# Sheet2.net
KiCad netlist of a schematic drawn in Altium Designer
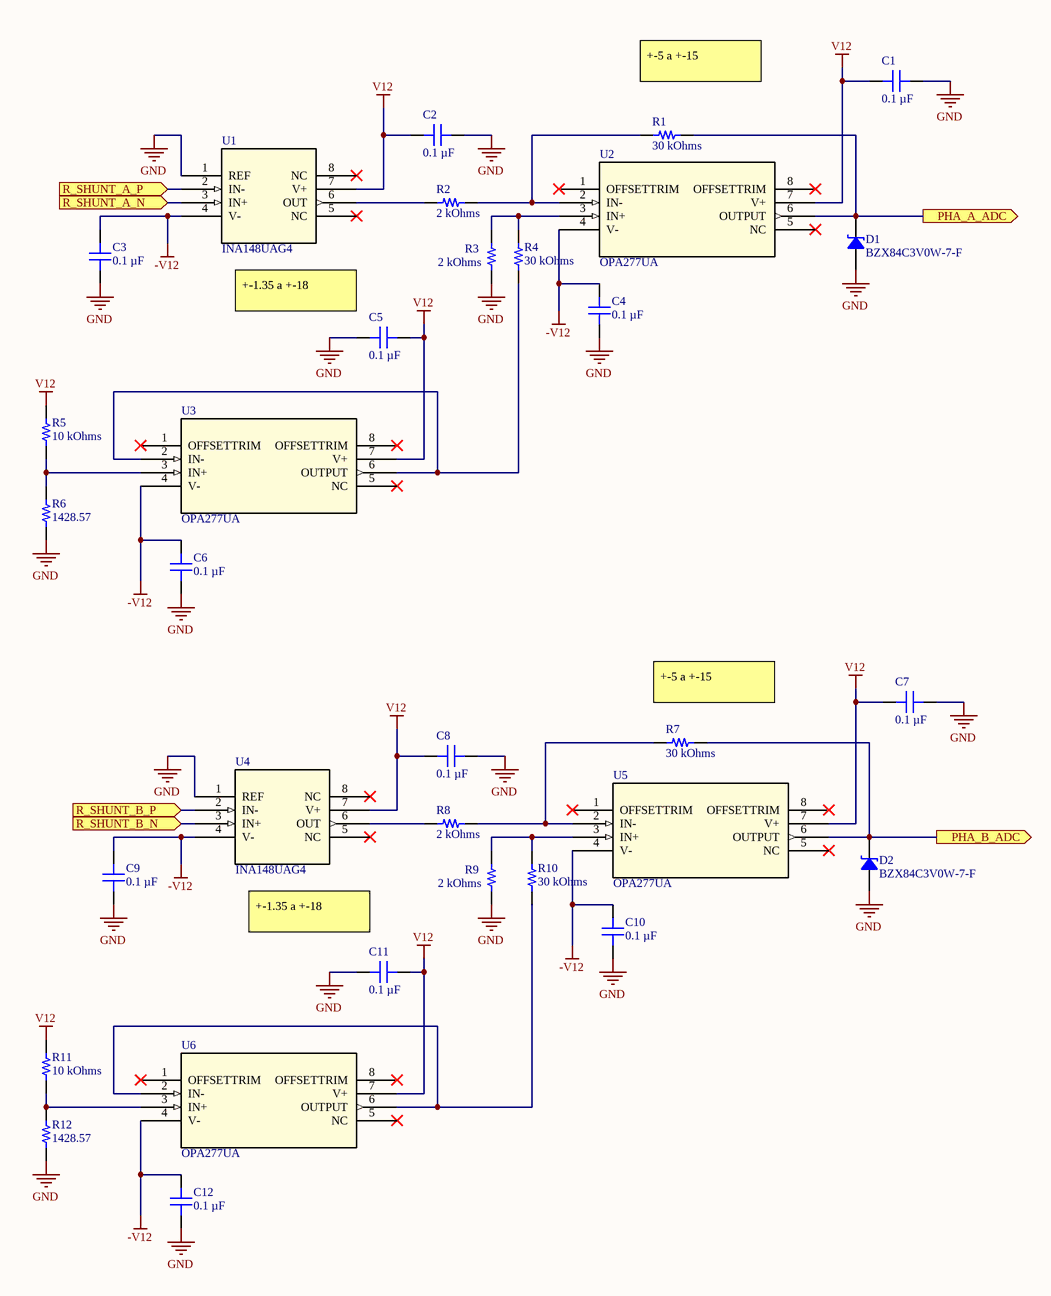
[diagram p0: Sheet2.SchDoc]

(export (version "E")
  (design (tool "Eeschema 10.0.6"))
  (components
    (comp (ref "C1")
      (value "0.1 µF")
      (footprint "CAP 0805_2012")
      (description "CAP CER 0.1UF 50V X7R 0805")
      (fields (field (name "PART NUMBER") "CC0805MRX7R9BB104") (field (name "MANUFACTURER") "Yageo"))
      (libsource (lib "Celestial Altium Library - altium_library") (part "Capacitor"))
    )
    (comp (ref "C2")
      (value "0.1 µF")
      (footprint "CAP 0805_2012")
      (description "CAP CER 0.1UF 50V X7R 0805")
      (fields (field (name "PART NUMBER") "CC0805MRX7R9BB104") (field (name "MANUFACTURER") "Yageo"))
      (libsource (lib "Celestial Altium Library - altium_library") (part "Capacitor"))
    )
    (comp (ref "C3")
      (value "0.1 µF")
      (footprint "CAP 0805_2012")
      (description "CAP CER 0.1UF 50V X7R 0805")
      (fields (field (name "PART NUMBER") "CC0805MRX7R9BB104") (field (name "MANUFACTURER") "Yageo"))
      (libsource (lib "Celestial Altium Library - altium_library") (part "Capacitor"))
    )
    (comp (ref "C4")
      (value "0.1 µF")
      (footprint "CAP 0805_2012")
      (description "CAP CER 0.1UF 50V X7R 0805")
      (fields (field (name "PART NUMBER") "CC0805MRX7R9BB104") (field (name "MANUFACTURER") "Yageo"))
      (libsource (lib "Celestial Altium Library - altium_library") (part "Capacitor"))
    )
    (comp (ref "C5")
      (value "0.1 µF")
      (footprint "CAP 0805_2012")
      (description "CAP CER 0.1UF 50V X7R 0805")
      (fields (field (name "PART NUMBER") "CC0805MRX7R9BB104") (field (name "MANUFACTURER") "Yageo"))
      (libsource (lib "Celestial Altium Library - altium_library") (part "Capacitor"))
    )
    (comp (ref "C6")
      (value "0.1 µF")
      (footprint "CAP 0805_2012")
      (description "CAP CER 0.1UF 50V X7R 0805")
      (fields (field (name "PART NUMBER") "CC0805MRX7R9BB104") (field (name "MANUFACTURER") "Yageo"))
      (libsource (lib "Celestial Altium Library - altium_library") (part "Capacitor"))
    )
    (comp (ref "C7")
      (value "0.1 µF")
      (footprint "CAP 0805_2012")
      (description "CAP CER 0.1UF 50V X7R 0805")
      (fields (field (name "PART NUMBER") "CC0805MRX7R9BB104") (field (name "MANUFACTURER") "Yageo"))
      (libsource (lib "Celestial Altium Library - altium_library") (part "Capacitor"))
    )
    (comp (ref "C8")
      (value "0.1 µF")
      (footprint "CAP 0805_2012")
      (description "CAP CER 0.1UF 50V X7R 0805")
      (fields (field (name "PART NUMBER") "CC0805MRX7R9BB104") (field (name "MANUFACTURER") "Yageo"))
      (libsource (lib "Celestial Altium Library - altium_library") (part "Capacitor"))
    )
    (comp (ref "C9")
      (value "0.1 µF")
      (footprint "CAP 0805_2012")
      (description "CAP CER 0.1UF 50V X7R 0805")
      (fields (field (name "PART NUMBER") "CC0805MRX7R9BB104") (field (name "MANUFACTURER") "Yageo"))
      (libsource (lib "Celestial Altium Library - altium_library") (part "Capacitor"))
    )
    (comp (ref "C10")
      (value "0.1 µF")
      (footprint "CAP 0805_2012")
      (description "CAP CER 0.1UF 50V X7R 0805")
      (fields (field (name "PART NUMBER") "CC0805MRX7R9BB104") (field (name "MANUFACTURER") "Yageo"))
      (libsource (lib "Celestial Altium Library - altium_library") (part "Capacitor"))
    )
    (comp (ref "C11")
      (value "0.1 µF")
      (footprint "CAP 0805_2012")
      (description "CAP CER 0.1UF 50V X7R 0805")
      (fields (field (name "PART NUMBER") "CC0805MRX7R9BB104") (field (name "MANUFACTURER") "Yageo"))
      (libsource (lib "Celestial Altium Library - altium_library") (part "Capacitor"))
    )
    (comp (ref "C12")
      (value "0.1 µF")
      (footprint "CAP 0805_2012")
      (description "CAP CER 0.1UF 50V X7R 0805")
      (fields (field (name "PART NUMBER") "CC0805MRX7R9BB104") (field (name "MANUFACTURER") "Yageo"))
      (libsource (lib "Celestial Altium Library - altium_library") (part "Capacitor"))
    )
    (comp (ref "D1")
      (value "BZX84C3V0W-7-F")
      (footprint "DIODES SOT-323-3")
      (description "DIODE ZENER 3V 200MW SOT323")
      (fields (field (name "MANUFACTURER") "Diodes Incorporated") (field (name "TOLERANCE") "±7%"))
      (libsource (lib "Celestial Altium Library - altium_library") (part "Diode Zener"))
    )
    (comp (ref "D2")
      (value "BZX84C3V0W-7-F")
      (footprint "DIODES SOT-323-3")
      (description "DIODE ZENER 3V 200MW SOT323")
      (fields (field (name "MANUFACTURER") "Diodes Incorporated") (field (name "TOLERANCE") "±7%"))
      (libsource (lib "Celestial Altium Library - altium_library") (part "Diode Zener"))
    )
    (comp (ref "R1")
      (value "30 kOhms")
      (footprint "RES 0805_2012")
      (description "RES SMD 200K OHM 5% 1/8W 0805")
      (fields (field (name "PART NUMBER") "CR0805-JW-204ELF") (field (name "MANUFACTURER") "Bourns Inc."))
      (libsource (lib "Celestial Altium Library - altium_library") (part "Resistor"))
    )
    (comp (ref "R2")
      (value "2 kOhms")
      (footprint "RES 0805_2012")
      (description "RES SMD 200K OHM 5% 1/8W 0805")
      (fields (field (name "PART NUMBER") "CR0805-JW-204ELF") (field (name "MANUFACTURER") "Bourns Inc."))
      (libsource (lib "Celestial Altium Library - altium_library") (part "Resistor"))
    )
    (comp (ref "R3")
      (value "2 kOhms")
      (footprint "RES 0805_2012")
      (description "RES SMD 200K OHM 5% 1/8W 0805")
      (fields (field (name "PART NUMBER") "CR0805-JW-204ELF") (field (name "MANUFACTURER") "Bourns Inc."))
      (libsource (lib "Celestial Altium Library - altium_library") (part "Resistor"))
    )
    (comp (ref "R4")
      (value "30 kOhms")
      (footprint "RES 0805_2012")
      (description "RES SMD 200K OHM 5% 1/8W 0805")
      (fields (field (name "PART NUMBER") "CR0805-JW-204ELF") (field (name "MANUFACTURER") "Bourns Inc."))
      (libsource (lib "Celestial Altium Library - altium_library") (part "Resistor"))
    )
    (comp (ref "R5")
      (value "10 kOhms")
      (footprint "RES 0805_2012")
      (description "RES SMD 200K OHM 5% 1/8W 0805")
      (fields (field (name "PART NUMBER") "CR0805-JW-204ELF") (field (name "MANUFACTURER") "Bourns Inc."))
      (libsource (lib "") (part "Resistor_1"))
    )
    (comp (ref "R6")
      (value "1428.57")
      (footprint "RES 0805_2012")
      (description "RES SMD 200K OHM 5% 1/8W 0805")
      (fields (field (name "PART NUMBER") "CR0805-JW-204ELF") (field (name "MANUFACTURER") "Bourns Inc."))
      (libsource (lib "Celestial Altium Library - altium_library") (part "Resistor"))
    )
    (comp (ref "R7")
      (value "30 kOhms")
      (footprint "RES 0805_2012")
      (description "RES SMD 200K OHM 5% 1/8W 0805")
      (fields (field (name "PART NUMBER") "CR0805-JW-204ELF") (field (name "MANUFACTURER") "Bourns Inc."))
      (libsource (lib "") (part "Resistor_1"))
    )
    (comp (ref "R8")
      (value "2 kOhms")
      (footprint "RES 0805_2012")
      (description "RES SMD 200K OHM 5% 1/8W 0805")
      (fields (field (name "PART NUMBER") "CR0805-JW-204ELF") (field (name "MANUFACTURER") "Bourns Inc."))
      (libsource (lib "Celestial Altium Library - altium_library") (part "Resistor"))
    )
    (comp (ref "R9")
      (value "2 kOhms")
      (footprint "RES 0805_2012")
      (description "RES SMD 200K OHM 5% 1/8W 0805")
      (fields (field (name "PART NUMBER") "CR0805-JW-204ELF") (field (name "MANUFACTURER") "Bourns Inc."))
      (libsource (lib "Celestial Altium Library - altium_library") (part "Resistor"))
    )
    (comp (ref "R10")
      (value "30 kOhms")
      (footprint "RES 0805_2012")
      (description "RES SMD 200K OHM 5% 1/8W 0805")
      (fields (field (name "PART NUMBER") "CR0805-JW-204ELF") (field (name "MANUFACTURER") "Bourns Inc."))
      (libsource (lib "Celestial Altium Library - altium_library") (part "Resistor"))
    )
    (comp (ref "R11")
      (value "10 kOhms")
      (footprint "RES 0805_2012")
      (description "RES SMD 200K OHM 5% 1/8W 0805")
      (fields (field (name "PART NUMBER") "CR0805-JW-204ELF") (field (name "MANUFACTURER") "Bourns Inc."))
      (libsource (lib "") (part "Resistor_1"))
    )
    (comp (ref "R12")
      (value "1428.57")
      (footprint "RES 0805_2012")
      (description "RES SMD 200K OHM 5% 1/8W 0805")
      (fields (field (name "PART NUMBER") "CR0805-JW-204ELF") (field (name "MANUFACTURER") "Bourns Inc."))
      (libsource (lib "Celestial Altium Library - altium_library") (part "Resistor"))
    )
    (comp (ref "U1")
      (value "INA148UAG4")
      (footprint "D8")
      (description "No Description Available")
      (fields (field (name "COPYRIGHT") "Copyright (C) 2023 Ultra Librarian. All rights reserved."))
      (libsource (lib "INA148UAG4") (part "INA148UAG4"))
    )
    (comp (ref "U2")
      (value "OPA277UA")
      (footprint "D8")
      (description "No Description Available")
      (fields (field (name "COPYRIGHT") "Copyright (C) 2023 Ultra Librarian. All rights reserved."))
      (libsource (lib "OPA277UA") (part "OPA277UA"))
    )
    (comp (ref "U3")
      (value "OPA277UA")
      (footprint "D8")
      (description "No Description Available")
      (fields (field (name "COPYRIGHT") "Copyright (C) 2023 Ultra Librarian. All rights reserved."))
      (libsource (lib "OPA277UA") (part "OPA277UA"))
    )
    (comp (ref "U4")
      (value "INA148UAG4")
      (footprint "D8")
      (description "No Description Available")
      (fields (field (name "COPYRIGHT") "Copyright (C) 2023 Ultra Librarian. All rights reserved."))
      (libsource (lib "INA148UAG4") (part "INA148UAG4"))
    )
    (comp (ref "U5")
      (value "OPA277UA")
      (footprint "D8")
      (description "No Description Available")
      (fields (field (name "COPYRIGHT") "Copyright (C) 2023 Ultra Librarian. All rights reserved."))
      (libsource (lib "OPA277UA") (part "OPA277UA"))
    )
    (comp (ref "U6")
      (value "OPA277UA")
      (footprint "D8")
      (description "No Description Available")
      (fields (field (name "COPYRIGHT") "Copyright (C) 2023 Ultra Librarian. All rights reserved."))
      (libsource (lib "OPA277UA") (part "OPA277UA"))
    )
  )
  (nets
    (net (code "1") (name "-V12") (class "Default")
      (node (ref "C10") (pin "2") (pinfunction "2_2") (pintype "passive"))
      (node (ref "C12") (pin "2") (pinfunction "2_2") (pintype "passive"))
      (node (ref "C3") (pin "2") (pinfunction "2_2") (pintype "passive"))
      (node (ref "C4") (pin "2") (pinfunction "2_2") (pintype "passive"))
      (node (ref "C6") (pin "2") (pinfunction "2_2") (pintype "passive"))
      (node (ref "C9") (pin "2") (pinfunction "2_2") (pintype "passive"))
      (node (ref "U1") (pin "4") (pinfunction "V-_4") (pintype "power_in"))
      (node (ref "U2") (pin "4") (pinfunction "V-_4") (pintype "power_in"))
      (node (ref "U3") (pin "4") (pinfunction "V-_4") (pintype "power_in"))
      (node (ref "U4") (pin "4") (pinfunction "V-_4") (pintype "power_in"))
      (node (ref "U5") (pin "4") (pinfunction "V-_4") (pintype "power_in"))
      (node (ref "U6") (pin "4") (pinfunction "V-_4") (pintype "power_in"))
    )
    (net (code "2") (name "/PHA_A_ADC") (class "Default")
      (node (ref "D1") (pin "2") (pinfunction "2_2") (pintype "passive"))
      (node (ref "R1") (pin "1") (pinfunction "1_1") (pintype "passive"))
      (node (ref "U2") (pin "6") (pinfunction "OUTPUT_6") (pintype "output"))
    )
    (net (code "3") (name "/PHA_B_ADC") (class "Default")
      (node (ref "D2") (pin "2") (pinfunction "2_2") (pintype "passive"))
      (node (ref "R7") (pin "1") (pinfunction "1_1") (pintype "passive"))
      (node (ref "U5") (pin "6") (pinfunction "OUTPUT_6") (pintype "output"))
    )
    (net (code "4") (name "/R_SHUNT_A_N") (class "Default")
      (node (ref "U1") (pin "3") (pinfunction "IN+_3") (pintype "input"))
    )
    (net (code "5") (name "/R_SHUNT_A_P") (class "Default")
      (node (ref "U1") (pin "2") (pinfunction "IN-_2") (pintype "input"))
    )
    (net (code "6") (name "/R_SHUNT_B_N") (class "Default")
      (node (ref "U4") (pin "3") (pinfunction "IN+_3") (pintype "input"))
    )
    (net (code "7") (name "/R_SHUNT_B_P") (class "Default")
      (node (ref "U4") (pin "2") (pinfunction "IN-_2") (pintype "input"))
    )
    (net (code "8") (name "GND") (class "Default")
      (node (ref "C1") (pin "2") (pinfunction "2_2") (pintype "passive"))
      (node (ref "C10") (pin "1") (pinfunction "1_1") (pintype "passive"))
      (node (ref "C11") (pin "2") (pinfunction "2_2") (pintype "passive"))
      (node (ref "C12") (pin "1") (pinfunction "1_1") (pintype "passive"))
      (node (ref "C2") (pin "2") (pinfunction "2_2") (pintype "passive"))
      (node (ref "C3") (pin "1") (pinfunction "1_1") (pintype "passive"))
      (node (ref "C4") (pin "1") (pinfunction "1_1") (pintype "passive"))
      (node (ref "C5") (pin "2") (pinfunction "2_2") (pintype "passive"))
      (node (ref "C6") (pin "1") (pinfunction "1_1") (pintype "passive"))
      (node (ref "C7") (pin "2") (pinfunction "2_2") (pintype "passive"))
      (node (ref "C8") (pin "2") (pinfunction "2_2") (pintype "passive"))
      (node (ref "C9") (pin "1") (pinfunction "1_1") (pintype "passive"))
      (node (ref "D1") (pin "1") (pinfunction "1_1") (pintype "passive"))
      (node (ref "D2") (pin "1") (pinfunction "1_1") (pintype "passive"))
      (node (ref "R12") (pin "2") (pinfunction "2_2") (pintype "passive"))
      (node (ref "R3") (pin "1") (pinfunction "1_1") (pintype "passive"))
      (node (ref "R6") (pin "2") (pinfunction "2_2") (pintype "passive"))
      (node (ref "R9") (pin "2") (pinfunction "2_2") (pintype "passive"))
      (node (ref "U1") (pin "1") (pinfunction "REF_1") (pintype "passive"))
      (node (ref "U4") (pin "1") (pinfunction "REF_1") (pintype "passive"))
    )
    (net (code "9") (name "Net-(U1-OUT)") (class "Default")
      (node (ref "R2") (pin "2") (pinfunction "2_2") (pintype "passive"))
      (node (ref "U1") (pin "6") (pinfunction "OUT_6") (pintype "output"))
    )
    (net (code "10") (name "Net-(U2-IN+)") (class "Default")
      (node (ref "R3") (pin "2") (pinfunction "2_2") (pintype "passive"))
      (node (ref "R4") (pin "1") (pinfunction "1_1") (pintype "passive"))
      (node (ref "U2") (pin "3") (pinfunction "IN+_3") (pintype "input"))
    )
    (net (code "11") (name "Net-(U2-IN-)") (class "Default")
      (node (ref "R1") (pin "2") (pinfunction "2_2") (pintype "passive"))
      (node (ref "R2") (pin "1") (pinfunction "1_1") (pintype "passive"))
      (node (ref "U2") (pin "2") (pinfunction "IN-_2") (pintype "input"))
    )
    (net (code "12") (name "Net-(U3-IN+)") (class "Default")
      (node (ref "R5") (pin "1") (pinfunction "1_1") (pintype "passive"))
      (node (ref "R6") (pin "1") (pinfunction "1_1") (pintype "passive"))
      (node (ref "U3") (pin "3") (pinfunction "IN+_3") (pintype "input"))
    )
    (net (code "13") (name "Net-(U3-IN-)") (class "Default")
      (node (ref "R4") (pin "2") (pinfunction "2_2") (pintype "passive"))
      (node (ref "U3") (pin "2") (pinfunction "IN-_2") (pintype "input"))
      (node (ref "U3") (pin "6") (pinfunction "OUTPUT_6") (pintype "output"))
    )
    (net (code "14") (name "Net-(U4-OUT)") (class "Default")
      (node (ref "R8") (pin "1") (pinfunction "1_1") (pintype "passive"))
      (node (ref "U4") (pin "6") (pinfunction "OUT_6") (pintype "output"))
    )
    (net (code "15") (name "Net-(U5-IN+)") (class "Default")
      (node (ref "R10") (pin "1") (pinfunction "1_1") (pintype "passive"))
      (node (ref "R9") (pin "1") (pinfunction "1_1") (pintype "passive"))
      (node (ref "U5") (pin "3") (pinfunction "IN+_3") (pintype "input"))
    )
    (net (code "16") (name "Net-(U5-IN-)") (class "Default")
      (node (ref "R7") (pin "1") (pinfunction "1_1") (pintype "passive"))
      (node (ref "R8") (pin "2") (pinfunction "2_2") (pintype "passive"))
      (node (ref "U5") (pin "2") (pinfunction "IN-_2") (pintype "input"))
    )
    (net (code "17") (name "Net-(U6-IN+)") (class "Default")
      (node (ref "R11") (pin "1") (pinfunction "1_1") (pintype "passive"))
      (node (ref "R12") (pin "1") (pinfunction "1_1") (pintype "passive"))
      (node (ref "U6") (pin "3") (pinfunction "IN+_3") (pintype "input"))
    )
    (net (code "18") (name "Net-(U6-IN-)") (class "Default")
      (node (ref "R10") (pin "2") (pinfunction "2_2") (pintype "passive"))
      (node (ref "U6") (pin "2") (pinfunction "IN-_2") (pintype "input"))
      (node (ref "U6") (pin "6") (pinfunction "OUTPUT_6") (pintype "output"))
    )
    (net (code "19") (name "V12") (class "Default")
      (node (ref "C1") (pin "1") (pinfunction "1_1") (pintype "passive"))
      (node (ref "C11") (pin "1") (pinfunction "1_1") (pintype "passive"))
      (node (ref "C2") (pin "1") (pinfunction "1_1") (pintype "passive"))
      (node (ref "C5") (pin "1") (pinfunction "1_1") (pintype "passive"))
      (node (ref "C7") (pin "1") (pinfunction "1_1") (pintype "passive"))
      (node (ref "C8") (pin "1") (pinfunction "1_1") (pintype "passive"))
      (node (ref "R11") (pin "1") (pinfunction "1_1") (pintype "passive"))
      (node (ref "R5") (pin "1") (pinfunction "1_1") (pintype "passive"))
      (node (ref "U1") (pin "7") (pinfunction "V+_7") (pintype "power_in"))
      (node (ref "U2") (pin "7") (pinfunction "V+_7") (pintype "power_in"))
      (node (ref "U3") (pin "7") (pinfunction "V+_7") (pintype "power_in"))
      (node (ref "U4") (pin "7") (pinfunction "V+_7") (pintype "power_in"))
      (node (ref "U5") (pin "7") (pinfunction "V+_7") (pintype "power_in"))
      (node (ref "U6") (pin "7") (pinfunction "V+_7") (pintype "power_in"))
    )
    (net (code "20") (name "unconnected-(U1-NC-Pad5)") (class "Default")
      (node (ref "U1") (pin "5") (pinfunction "NC_5") (pintype "passive+no_connect"))
    )
    (net (code "21") (name "unconnected-(U1-NC-Pad8)") (class "Default")
      (node (ref "U1") (pin "8") (pinfunction "NC_8") (pintype "passive+no_connect"))
    )
    (net (code "22") (name "unconnected-(U2-NC-Pad5)") (class "Default")
      (node (ref "U2") (pin "5") (pinfunction "NC_5") (pintype "passive+no_connect"))
    )
    (net (code "23") (name "unconnected-(U2-OFFSETTRIM-Pad1)") (class "Default")
      (node (ref "U2") (pin "1") (pinfunction "OFFSETTRIM_1") (pintype "passive+no_connect"))
    )
    (net (code "24") (name "unconnected-(U2-OFFSETTRIM-Pad8)") (class "Default")
      (node (ref "U2") (pin "8") (pinfunction "OFFSETTRIM_8") (pintype "passive+no_connect"))
    )
    (net (code "25") (name "unconnected-(U3-NC-Pad5)") (class "Default")
      (node (ref "U3") (pin "5") (pinfunction "NC_5") (pintype "passive+no_connect"))
    )
    (net (code "26") (name "unconnected-(U3-OFFSETTRIM-Pad1)") (class "Default")
      (node (ref "U3") (pin "1") (pinfunction "OFFSETTRIM_1") (pintype "passive+no_connect"))
    )
    (net (code "27") (name "unconnected-(U3-OFFSETTRIM-Pad8)") (class "Default")
      (node (ref "U3") (pin "8") (pinfunction "OFFSETTRIM_8") (pintype "passive+no_connect"))
    )
    (net (code "28") (name "unconnected-(U4-NC-Pad5)") (class "Default")
      (node (ref "U4") (pin "5") (pinfunction "NC_5") (pintype "passive+no_connect"))
    )
    (net (code "29") (name "unconnected-(U4-NC-Pad8)") (class "Default")
      (node (ref "U4") (pin "8") (pinfunction "NC_8") (pintype "passive+no_connect"))
    )
    (net (code "30") (name "unconnected-(U5-NC-Pad5)") (class "Default")
      (node (ref "U5") (pin "5") (pinfunction "NC_5") (pintype "passive+no_connect"))
    )
    (net (code "31") (name "unconnected-(U5-OFFSETTRIM-Pad1)") (class "Default")
      (node (ref "U5") (pin "1") (pinfunction "OFFSETTRIM_1") (pintype "passive+no_connect"))
    )
    (net (code "32") (name "unconnected-(U5-OFFSETTRIM-Pad8)") (class "Default")
      (node (ref "U5") (pin "8") (pinfunction "OFFSETTRIM_8") (pintype "passive+no_connect"))
    )
    (net (code "33") (name "unconnected-(U6-NC-Pad5)") (class "Default")
      (node (ref "U6") (pin "5") (pinfunction "NC_5") (pintype "passive+no_connect"))
    )
    (net (code "34") (name "unconnected-(U6-OFFSETTRIM-Pad1)") (class "Default")
      (node (ref "U6") (pin "1") (pinfunction "OFFSETTRIM_1") (pintype "passive+no_connect"))
    )
    (net (code "35") (name "unconnected-(U6-OFFSETTRIM-Pad8)") (class "Default")
      (node (ref "U6") (pin "8") (pinfunction "OFFSETTRIM_8") (pintype "passive+no_connect"))
    )
  )
)
